# SP26_Knockoffvendingmachine_PCBjson_Nath.net
KiCad netlist of a schematic drawn in EasyEDA
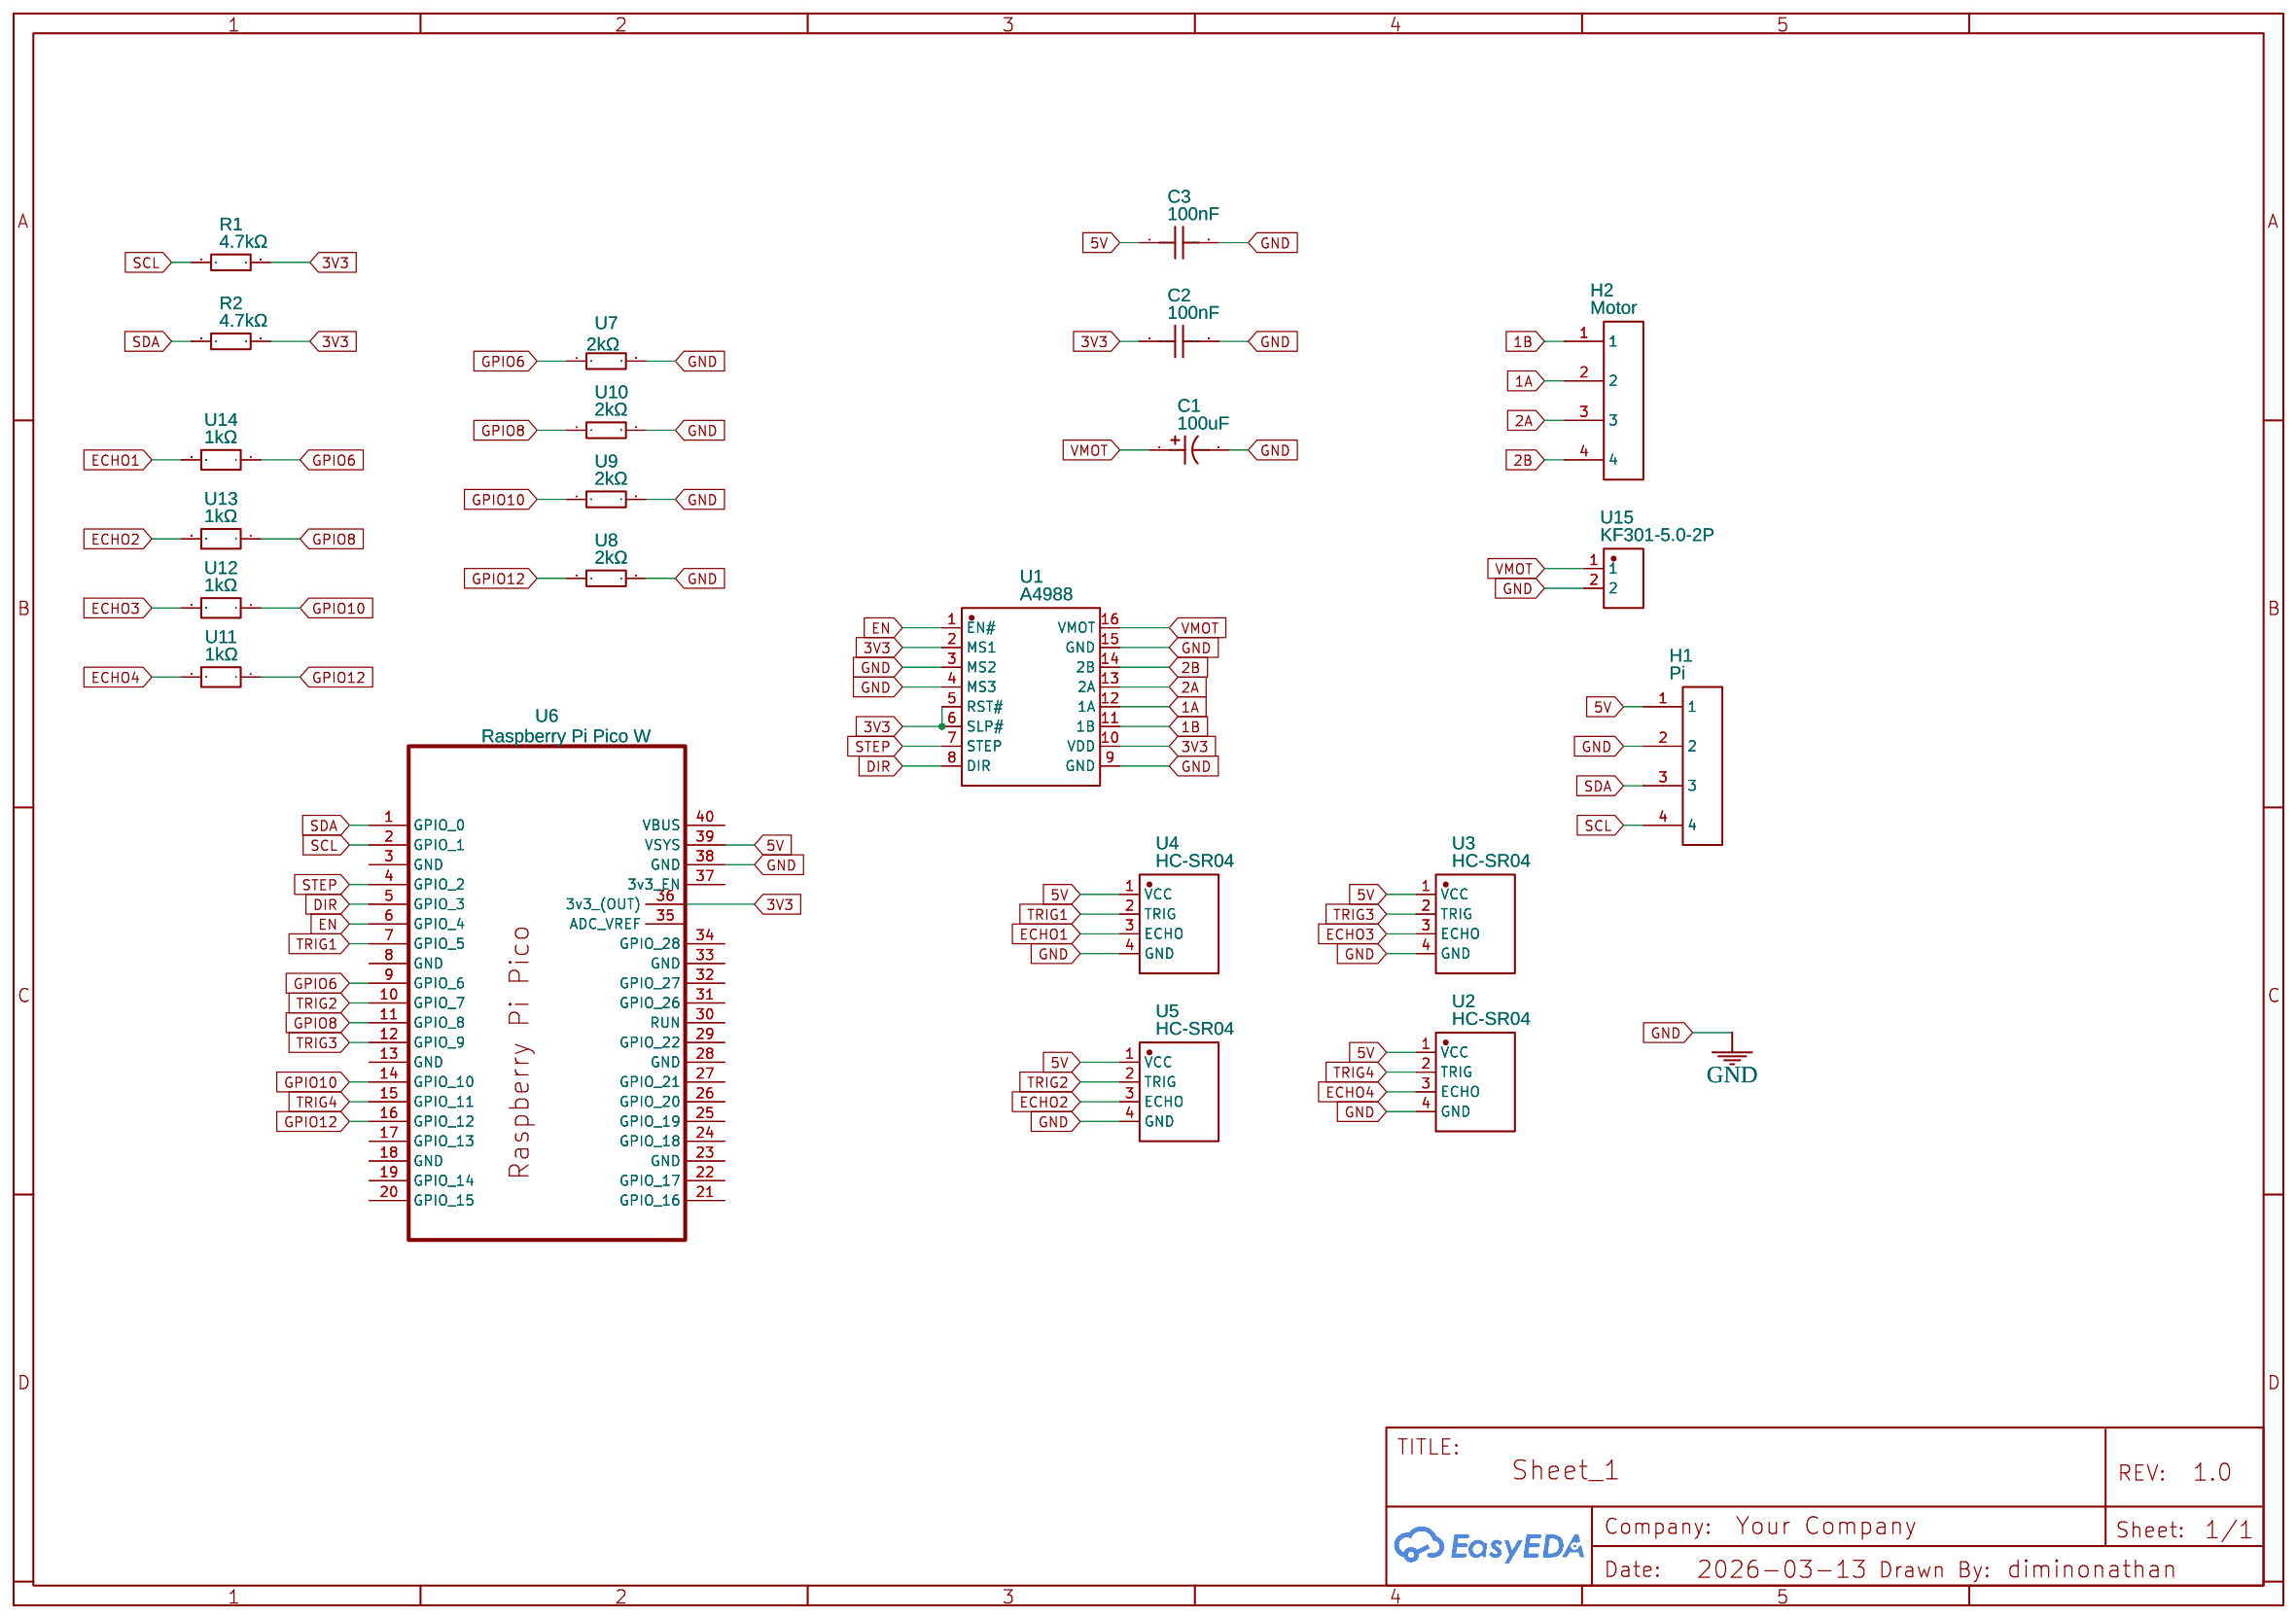
[diagram p0: schematic sheet]

(export (version "E")
  (design (tool "Eeschema 10.0.6"))
  (components
    (comp (ref "C1")
      (value "100uF")
      (fields (field (name "Manufacturer Part") "RYHG35V100UF6*8") (field (name "Manufacturer") "HONOR(荣誉)"))
      (libsource (lib "") (part "RYHG35V100UF6*8"))
    )
    (comp (ref "C2")
      (value "100nF")
      (fields (field (name "Manufacturer Part") "CGA4J3X7T2E104M125AA") (field (name "Manufacturer") "TDK"))
      (libsource (lib "") (part "CGA4J3X7T2E104M125AA"))
    )
    (comp (ref "C3")
      (value "100nF")
      (fields (field (name "Manufacturer Part") "CGA4J3X7T2E104M125AA") (field (name "Manufacturer") "TDK"))
      (libsource (lib "") (part "CGA4J3X7T2E104M125AA"))
    )
    (comp (ref "H1")
      (value "Pi")
      (fields (field (name "Manufacturer Part") "2.00mm 1 x 4"))
      (libsource (lib "") (part "1x4 2.00mm header"))
    )
    (comp (ref "H2")
      (value "Motor")
      (fields (field (name "Manufacturer Part") "2.00mm 1 x 4"))
      (libsource (lib "") (part "1x4 2.00mm header"))
    )
    (comp (ref "R1")
      (value "4.7kΩ")
      (fields
        (field (name "Manufacturer Part") "MF1/2W-4.7KΩ±1% T")
        (field (name "Manufacturer") "CCO(千志电子)")
      )
      (libsource (lib "") (part "MF1/2W-4.7KΩ±1% T52"))
    )
    (comp (ref "R2")
      (value "4.7kΩ")
      (fields
        (field (name "Manufacturer Part") "MF1/2W-4.7KΩ±1% T")
        (field (name "Manufacturer") "CCO(千志电子)")
      )
      (libsource (lib "") (part "MF1/2W-4.7KΩ±1% T52"))
    )
    (comp (ref "U1") (value "A4988") (libsource (lib "") (part "A4988")))
    (comp (ref "U2")
      (value "HC-SR04")
      (fields (field (name "Manufacturer") "Universal Microelectronics"))
      (libsource (lib "") (part "HC-SR04"))
    )
    (comp (ref "U3")
      (value "HC-SR04")
      (fields (field (name "Manufacturer") "Universal Microelectronics"))
      (libsource (lib "") (part "HC-SR04"))
    )
    (comp (ref "U4")
      (value "HC-SR04")
      (fields (field (name "Manufacturer") "Universal Microelectronics"))
      (libsource (lib "") (part "HC-SR04"))
    )
    (comp (ref "U5")
      (value "HC-SR04")
      (fields (field (name "Manufacturer") "Universal Microelectronics"))
      (libsource (lib "") (part "HC-SR04"))
    )
    (comp (ref "U6") (value "Raspberry Pi Pico W") (libsource (lib "") (part "Raspberry Pi Pico W")))
    (comp (ref "U7")
      (value "2kΩ")
      (fields (field (name "Manufacturer Part") "MFR1WSFRE52-2K") (field (name "Manufacturer") "YAGEO(国巨)"))
      (libsource (lib "") (part "MFR1WSFRE52-2K"))
    )
    (comp (ref "U8")
      (value "2kΩ")
      (fields (field (name "Manufacturer Part") "MFR1WSFRE52-2K") (field (name "Manufacturer") "YAGEO(国巨)"))
      (libsource (lib "") (part "MFR1WSFRE52-2K"))
    )
    (comp (ref "U9")
      (value "2kΩ")
      (fields (field (name "Manufacturer Part") "MFR1WSFRE52-2K") (field (name "Manufacturer") "YAGEO(国巨)"))
      (libsource (lib "") (part "MFR1WSFRE52-2K"))
    )
    (comp (ref "U10")
      (value "2kΩ")
      (fields (field (name "Manufacturer Part") "MFR1WSFRE52-2K") (field (name "Manufacturer") "YAGEO(国巨)"))
      (libsource (lib "") (part "MFR1WSFRE52-2K"))
    )
    (comp (ref "U11")
      (value "1kΩ")
      (fields (field (name "Manufacturer Part") "SQP300JB-1K") (field (name "Manufacturer") "YAGEO(国巨)"))
      (libsource (lib "") (part "SQP300JB-1K"))
    )
    (comp (ref "U12")
      (value "1kΩ")
      (fields (field (name "Manufacturer Part") "SQP300JB-1K") (field (name "Manufacturer") "YAGEO(国巨)"))
      (libsource (lib "") (part "SQP300JB-1K"))
    )
    (comp (ref "U13")
      (value "1kΩ")
      (fields (field (name "Manufacturer Part") "SQP300JB-1K") (field (name "Manufacturer") "YAGEO(国巨)"))
      (libsource (lib "") (part "SQP300JB-1K"))
    )
    (comp (ref "U14")
      (value "1kΩ")
      (fields (field (name "Manufacturer Part") "SQP300JB-1K") (field (name "Manufacturer") "YAGEO(国巨)"))
      (libsource (lib "") (part "SQP300JB-1K"))
    )
    (comp (ref "U15")
      (value "KF301-5.0-2P")
      (fields (field (name "Manufacturer") "KEFA(科发)"))
      (libsource (lib "") (part "KF301-5.0-2P"))
    )
  )
  (nets
    (net (code "1") (name "1A") (class "Default")
      (node (ref "H2") (pin "2") (pinfunction "2_2") (pintype "unspecified"))
      (node (ref "U1") (pin "12") (pinfunction "1A_12") (pintype "unspecified"))
    )
    (net (code "2") (name "1B") (class "Default")
      (node (ref "H2") (pin "1") (pinfunction "1_1") (pintype "unspecified"))
      (node (ref "U1") (pin "11") (pinfunction "1B_11") (pintype "unspecified"))
    )
    (net (code "3") (name "2A") (class "Default")
      (node (ref "H2") (pin "3") (pinfunction "3_3") (pintype "unspecified"))
      (node (ref "U1") (pin "13") (pinfunction "2A_13") (pintype "unspecified"))
    )
    (net (code "4") (name "2B") (class "Default")
      (node (ref "H2") (pin "4") (pinfunction "4_4") (pintype "unspecified"))
      (node (ref "U1") (pin "14") (pinfunction "2B_14") (pintype "unspecified"))
    )
    (net (code "5") (name "3V3") (class "Default")
      (node (ref "C2") (pin "1") (pinfunction "1_1") (pintype "unspecified"))
      (node (ref "R1") (pin "2") (pinfunction "2_2") (pintype "unspecified"))
      (node (ref "R2") (pin "2") (pinfunction "2_2") (pintype "unspecified"))
      (node (ref "U1") (pin "10") (pinfunction "VDD_10") (pintype "unspecified"))
      (node (ref "U1") (pin "2") (pinfunction "MS1_2") (pintype "unspecified"))
      (node (ref "U1") (pin "5") (pinfunction "RST#_5") (pintype "unspecified"))
      (node (ref "U1") (pin "6") (pinfunction "SLP#_6") (pintype "unspecified"))
      (node (ref "U6") (pin "36") (pinfunction "3v3_(OUT)_36") (pintype "unspecified"))
    )
    (net (code "6") (name "5V") (class "Default")
      (node (ref "C3") (pin "1") (pinfunction "1_1") (pintype "unspecified"))
      (node (ref "H1") (pin "1") (pinfunction "1_1") (pintype "unspecified"))
      (node (ref "U2") (pin "1") (pinfunction "VCC_1") (pintype "unspecified"))
      (node (ref "U3") (pin "1") (pinfunction "VCC_1") (pintype "unspecified"))
      (node (ref "U4") (pin "1") (pinfunction "VCC_1") (pintype "unspecified"))
      (node (ref "U5") (pin "1") (pinfunction "VCC_1") (pintype "unspecified"))
      (node (ref "U6") (pin "39") (pinfunction "VSYS_39") (pintype "unspecified"))
    )
    (net (code "7") (name "DIR") (class "Default")
      (node (ref "U1") (pin "8") (pinfunction "DIR_8") (pintype "unspecified"))
      (node (ref "U6") (pin "5") (pinfunction "GPIO_3_5") (pintype "unspecified"))
    )
    (net (code "8") (name "ECHO1") (class "Default")
      (node (ref "U14") (pin "2") (pinfunction "2_2") (pintype "unspecified"))
      (node (ref "U4") (pin "3") (pinfunction "ECHO_3") (pintype "unspecified"))
    )
    (net (code "9") (name "ECHO2") (class "Default")
      (node (ref "U13") (pin "2") (pinfunction "2_2") (pintype "unspecified"))
      (node (ref "U5") (pin "3") (pinfunction "ECHO_3") (pintype "unspecified"))
    )
    (net (code "10") (name "ECHO3") (class "Default")
      (node (ref "U12") (pin "2") (pinfunction "2_2") (pintype "unspecified"))
      (node (ref "U3") (pin "3") (pinfunction "ECHO_3") (pintype "unspecified"))
    )
    (net (code "11") (name "ECHO4") (class "Default")
      (node (ref "U11") (pin "2") (pinfunction "2_2") (pintype "unspecified"))
      (node (ref "U2") (pin "3") (pinfunction "ECHO_3") (pintype "unspecified"))
    )
    (net (code "12") (name "EN") (class "Default")
      (node (ref "U1") (pin "1") (pinfunction "EN#_1") (pintype "unspecified"))
      (node (ref "U6") (pin "6") (pinfunction "GPIO_4_6") (pintype "unspecified"))
    )
    (net (code "13") (name "GND") (class "Default")
      (node (ref "C1") (pin "2") (pinfunction "2_2") (pintype "input"))
      (node (ref "C2") (pin "2") (pinfunction "2_2") (pintype "unspecified"))
      (node (ref "C3") (pin "2") (pinfunction "2_2") (pintype "unspecified"))
      (node (ref "H1") (pin "2") (pinfunction "2_2") (pintype "unspecified"))
      (node (ref "U1") (pin "15") (pinfunction "GND_15") (pintype "unspecified"))
      (node (ref "U1") (pin "3") (pinfunction "MS2_3") (pintype "unspecified"))
      (node (ref "U1") (pin "4") (pinfunction "MS3_4") (pintype "unspecified"))
      (node (ref "U1") (pin "9") (pinfunction "GND_9") (pintype "unspecified"))
      (node (ref "U10") (pin "2") (pinfunction "2_2") (pintype "unspecified"))
      (node (ref "U15") (pin "2") (pinfunction "2_2") (pintype "unspecified"))
      (node (ref "U2") (pin "4") (pinfunction "GND_4") (pintype "unspecified"))
      (node (ref "U3") (pin "4") (pinfunction "GND_4") (pintype "unspecified"))
      (node (ref "U4") (pin "4") (pinfunction "GND_4") (pintype "unspecified"))
      (node (ref "U5") (pin "4") (pinfunction "GND_4") (pintype "unspecified"))
      (node (ref "U6") (pin "38") (pinfunction "GND_38") (pintype "unspecified"))
      (node (ref "U7") (pin "2") (pinfunction "2_2") (pintype "unspecified"))
      (node (ref "U8") (pin "2") (pinfunction "2_2") (pintype "unspecified"))
      (node (ref "U9") (pin "2") (pinfunction "2_2") (pintype "unspecified"))
    )
    (net (code "14") (name "GPIO6") (class "Default")
      (node (ref "U14") (pin "1") (pinfunction "1_1") (pintype "unspecified"))
      (node (ref "U6") (pin "9") (pinfunction "GPIO_6_9") (pintype "unspecified"))
      (node (ref "U7") (pin "1") (pinfunction "1_1") (pintype "unspecified"))
    )
    (net (code "15") (name "GPIO8") (class "Default")
      (node (ref "U10") (pin "1") (pinfunction "1_1") (pintype "unspecified"))
      (node (ref "U13") (pin "1") (pinfunction "1_1") (pintype "unspecified"))
      (node (ref "U6") (pin "11") (pinfunction "GPIO_8_11") (pintype "unspecified"))
    )
    (net (code "16") (name "GPIO10") (class "Default")
      (node (ref "U12") (pin "1") (pinfunction "1_1") (pintype "unspecified"))
      (node (ref "U6") (pin "14") (pinfunction "GPIO_10_14") (pintype "unspecified"))
      (node (ref "U9") (pin "1") (pinfunction "1_1") (pintype "unspecified"))
    )
    (net (code "17") (name "GPIO12") (class "Default")
      (node (ref "U11") (pin "1") (pinfunction "1_1") (pintype "unspecified"))
      (node (ref "U6") (pin "16") (pinfunction "GPIO_12_16") (pintype "unspecified"))
      (node (ref "U8") (pin "1") (pinfunction "1_1") (pintype "unspecified"))
    )
    (net (code "18") (name "SCL") (class "Default")
      (node (ref "H1") (pin "4") (pinfunction "4_4") (pintype "unspecified"))
      (node (ref "R1") (pin "1") (pinfunction "1_1") (pintype "unspecified"))
      (node (ref "U6") (pin "2") (pinfunction "GPIO_1_2") (pintype "unspecified"))
    )
    (net (code "19") (name "SDA") (class "Default")
      (node (ref "H1") (pin "3") (pinfunction "3_3") (pintype "unspecified"))
      (node (ref "R2") (pin "1") (pinfunction "1_1") (pintype "unspecified"))
      (node (ref "U6") (pin "1") (pinfunction "GPIO_0_1") (pintype "unspecified"))
    )
    (net (code "20") (name "STEP") (class "Default")
      (node (ref "U1") (pin "7") (pinfunction "STEP_7") (pintype "unspecified"))
      (node (ref "U6") (pin "4") (pinfunction "GPIO_2_4") (pintype "unspecified"))
    )
    (net (code "21") (name "TRIG1") (class "Default")
      (node (ref "U4") (pin "2") (pinfunction "TRIG_2") (pintype "unspecified"))
      (node (ref "U6") (pin "7") (pinfunction "GPIO_5_7") (pintype "unspecified"))
    )
    (net (code "22") (name "TRIG2") (class "Default")
      (node (ref "U5") (pin "2") (pinfunction "TRIG_2") (pintype "unspecified"))
      (node (ref "U6") (pin "10") (pinfunction "GPIO_7_10") (pintype "unspecified"))
    )
    (net (code "23") (name "TRIG3") (class "Default")
      (node (ref "U3") (pin "2") (pinfunction "TRIG_2") (pintype "unspecified"))
      (node (ref "U6") (pin "12") (pinfunction "GPIO_9_12") (pintype "unspecified"))
    )
    (net (code "24") (name "TRIG4") (class "Default")
      (node (ref "U2") (pin "2") (pinfunction "TRIG_2") (pintype "unspecified"))
      (node (ref "U6") (pin "15") (pinfunction "GPIO_11_15") (pintype "unspecified"))
    )
    (net (code "25") (name "VMOT") (class "Default")
      (node (ref "C1") (pin "1") (pinfunction "1_1") (pintype "input"))
      (node (ref "U1") (pin "16") (pinfunction "VMOT_16") (pintype "unspecified"))
      (node (ref "U15") (pin "1") (pinfunction "1_1") (pintype "unspecified"))
    )
    (net (code "26") (name "unconnected-(U6-3v3_EN-Pad37)") (class "Default")
      (node (ref "U6") (pin "37") (pinfunction "3v3_EN_37") (pintype "unspecified"))
    )
    (net (code "27") (name "unconnected-(U6-ADC_VREF-Pad35)") (class "Default")
      (node (ref "U6") (pin "35") (pinfunction "ADC_VREF_35") (pintype "unspecified"))
    )
    (net (code "28") (name "unconnected-(U6-GND-Pad3)") (class "Default")
      (node (ref "U6") (pin "3") (pinfunction "GND_3") (pintype "unspecified"))
    )
    (net (code "29") (name "unconnected-(U6-GND-Pad8)") (class "Default")
      (node (ref "U6") (pin "8") (pinfunction "GND_8") (pintype "unspecified"))
    )
    (net (code "30") (name "unconnected-(U6-GND-Pad13)") (class "Default")
      (node (ref "U6") (pin "13") (pinfunction "GND_13") (pintype "unspecified"))
    )
    (net (code "31") (name "unconnected-(U6-GND-Pad18)") (class "Default")
      (node (ref "U6") (pin "18") (pinfunction "GND_18") (pintype "unspecified"))
    )
    (net (code "32") (name "unconnected-(U6-GND-Pad23)") (class "Default")
      (node (ref "U6") (pin "23") (pinfunction "GND_23") (pintype "unspecified"))
    )
    (net (code "33") (name "unconnected-(U6-GND-Pad28)") (class "Default")
      (node (ref "U6") (pin "28") (pinfunction "GND_28") (pintype "unspecified"))
    )
    (net (code "34") (name "unconnected-(U6-GND-Pad33)") (class "Default")
      (node (ref "U6") (pin "33") (pinfunction "GND_33") (pintype "unspecified"))
    )
    (net (code "35") (name "unconnected-(U6-GPIO_13-Pad17)") (class "Default")
      (node (ref "U6") (pin "17") (pinfunction "GPIO_13_17") (pintype "unspecified"))
    )
    (net (code "36") (name "unconnected-(U6-GPIO_14-Pad19)") (class "Default")
      (node (ref "U6") (pin "19") (pinfunction "GPIO_14_19") (pintype "unspecified"))
    )
    (net (code "37") (name "unconnected-(U6-GPIO_15-Pad20)") (class "Default")
      (node (ref "U6") (pin "20") (pinfunction "GPIO_15_20") (pintype "unspecified"))
    )
    (net (code "38") (name "unconnected-(U6-GPIO_16-Pad21)") (class "Default")
      (node (ref "U6") (pin "21") (pinfunction "GPIO_16_21") (pintype "unspecified"))
    )
    (net (code "39") (name "unconnected-(U6-GPIO_17-Pad22)") (class "Default")
      (node (ref "U6") (pin "22") (pinfunction "GPIO_17_22") (pintype "unspecified"))
    )
    (net (code "40") (name "unconnected-(U6-GPIO_18-Pad24)") (class "Default")
      (node (ref "U6") (pin "24") (pinfunction "GPIO_18_24") (pintype "unspecified"))
    )
    (net (code "41") (name "unconnected-(U6-GPIO_19-Pad25)") (class "Default")
      (node (ref "U6") (pin "25") (pinfunction "GPIO_19_25") (pintype "unspecified"))
    )
    (net (code "42") (name "unconnected-(U6-GPIO_20-Pad26)") (class "Default")
      (node (ref "U6") (pin "26") (pinfunction "GPIO_20_26") (pintype "unspecified"))
    )
    (net (code "43") (name "unconnected-(U6-GPIO_21-Pad27)") (class "Default")
      (node (ref "U6") (pin "27") (pinfunction "GPIO_21_27") (pintype "unspecified"))
    )
    (net (code "44") (name "unconnected-(U6-GPIO_22-Pad29)") (class "Default")
      (node (ref "U6") (pin "29") (pinfunction "GPIO_22_29") (pintype "unspecified"))
    )
    (net (code "45") (name "unconnected-(U6-GPIO_26-Pad31)") (class "Default")
      (node (ref "U6") (pin "31") (pinfunction "GPIO_26_31") (pintype "unspecified"))
    )
    (net (code "46") (name "unconnected-(U6-GPIO_27-Pad32)") (class "Default")
      (node (ref "U6") (pin "32") (pinfunction "GPIO_27_32") (pintype "unspecified"))
    )
    (net (code "47") (name "unconnected-(U6-GPIO_28-Pad34)") (class "Default")
      (node (ref "U6") (pin "34") (pinfunction "GPIO_28_34") (pintype "unspecified"))
    )
    (net (code "48") (name "unconnected-(U6-RUN-Pad30)") (class "Default")
      (node (ref "U6") (pin "30") (pinfunction "RUN_30") (pintype "unspecified"))
    )
    (net (code "49") (name "unconnected-(U6-VBUS-Pad40)") (class "Default")
      (node (ref "U6") (pin "40") (pinfunction "VBUS_40") (pintype "unspecified"))
    )
  )
)
